# untitled.net
KiCad netlist of a schematic drawn in EAGLE
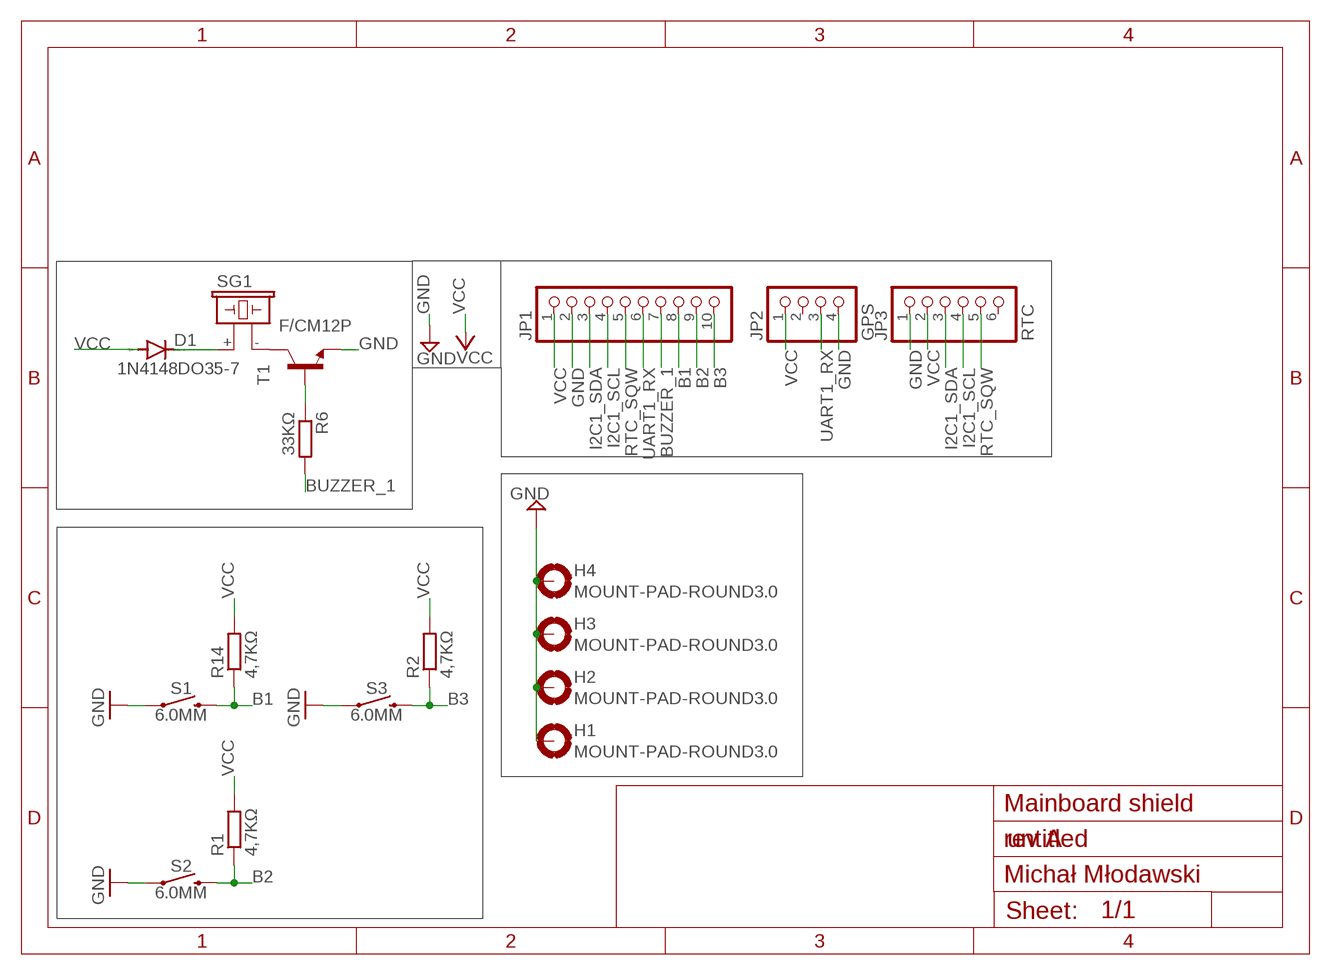
[diagram p0: schematic, sheet 1]

(export (version "E")
  (design (tool "Eeschema 10.0.6"))
  (components
    (comp (ref "D1")
      (value "1N4148DO35-7")
      (footprint "eagle-import:DO35-7")
      (libsource (lib "eagle-import") (part "1N4148DO35-7"))
    )
    (comp (ref "H1")
      (value "MOUNT-PAD-ROUND3.0")
      (footprint "eagle-import:3,0-PAD")
      (libsource (lib "eagle-import") (part "MOUNT-PAD-ROUND3.0"))
    )
    (comp (ref "H2")
      (value "MOUNT-PAD-ROUND3.0")
      (footprint "eagle-import:3,0-PAD")
      (libsource (lib "eagle-import") (part "MOUNT-PAD-ROUND3.0"))
    )
    (comp (ref "H3")
      (value "MOUNT-PAD-ROUND3.0")
      (footprint "eagle-import:3,0-PAD")
      (libsource (lib "eagle-import") (part "MOUNT-PAD-ROUND3.0"))
    )
    (comp (ref "H4")
      (value "MOUNT-PAD-ROUND3.0")
      (footprint "eagle-import:3,0-PAD")
      (libsource (lib "eagle-import") (part "MOUNT-PAD-ROUND3.0"))
    )
    (comp (ref "JP1")
      (value "PINHD-1X10")
      (footprint "eagle-import:1X10")
      (libsource (lib "eagle-import") (part "PINHD-1X10"))
    )
    (comp (ref "JP2")
      (value "GPS")
      (footprint "eagle-import:1X04")
      (libsource (lib "eagle-import") (part "PINHD-1X4"))
    )
    (comp (ref "JP3")
      (value "RTC")
      (footprint "eagle-import:1X06")
      (libsource (lib "eagle-import") (part "PINHD-1X6"))
    )
    (comp (ref "R1")
      (value "4,7KΩ")
      (footprint "eagle-import:R1206")
      (libsource (lib "eagle-import") (part "R-EU_R1206"))
    )
    (comp (ref "R2")
      (value "4,7KΩ")
      (footprint "eagle-import:R1206")
      (libsource (lib "eagle-import") (part "R-EU_R1206"))
    )
    (comp (ref "R6")
      (value "33KΩ")
      (footprint "eagle-import:R1206")
      (libsource (lib "eagle-import") (part "R-EU_R1206"))
    )
    (comp (ref "R14")
      (value "4,7KΩ")
      (footprint "eagle-import:R1206")
      (libsource (lib "eagle-import") (part "R-EU_R1206"))
    )
    (comp (ref "S1")
      (value "6.0MM")
      (footprint "eagle-import:TACTILE_SWITCH_PTH_6.0MM")
      (libsource (lib "eagle-import") (part "MOMENTARY-SWITCH-SPST-PTH-6.0MM"))
    )
    (comp (ref "S2")
      (value "6.0MM")
      (footprint "eagle-import:TACTILE_SWITCH_PTH_6.0MM")
      (libsource (lib "eagle-import") (part "MOMENTARY-SWITCH-SPST-PTH-6.0MM"))
    )
    (comp (ref "S3")
      (value "6.0MM")
      (footprint "eagle-import:TACTILE_SWITCH_PTH_6.0MM")
      (libsource (lib "eagle-import") (part "MOMENTARY-SWITCH-SPST-PTH-6.0MM"))
    )
    (comp (ref "SG1")
      (value "F/CM12P")
      (footprint "eagle-import:F_CM12P")
      (libsource (lib "eagle-import") (part "F/CM12P"))
    )
    (comp (ref "T1")
      (value "BC548-NPN-TO92-CBE")
      (footprint "eagle-import:TO92-CBE")
      (libsource (lib "eagle-import") (part "-NPN-TO92-CBEBC548"))
    )
  )
  (nets
    (net (code "1") (name "/B1") (class "Default")
      (node (ref "JP1") (pin "8") (pinfunction "8_8") (pintype "passive"))
      (node (ref "R14") (pin "1") (pinfunction "1_1") (pintype "passive"))
      (node (ref "S1") (pin "3") (pinfunction "2_3") (pintype "passive"))
    )
    (net (code "2") (name "/B2") (class "Default")
      (node (ref "JP1") (pin "9") (pinfunction "9_9") (pintype "passive"))
      (node (ref "R1") (pin "1") (pinfunction "1_1") (pintype "passive"))
      (node (ref "S2") (pin "3") (pinfunction "2_3") (pintype "passive"))
    )
    (net (code "3") (name "/B3") (class "Default")
      (node (ref "JP1") (pin "10") (pinfunction "10_10") (pintype "passive"))
      (node (ref "R2") (pin "1") (pinfunction "1_1") (pintype "passive"))
      (node (ref "S3") (pin "3") (pinfunction "2_3") (pintype "passive"))
    )
    (net (code "4") (name "/BUZZER_1") (class "Default")
      (node (ref "JP1") (pin "7") (pinfunction "7_7") (pintype "passive"))
      (node (ref "R6") (pin "2") (pinfunction "2_2") (pintype "passive"))
    )
    (net (code "5") (name "/I2C1_SCL") (class "Default")
      (node (ref "JP1") (pin "4") (pinfunction "4_4") (pintype "passive"))
      (node (ref "JP3") (pin "4") (pinfunction "4_4") (pintype "passive"))
    )
    (net (code "6") (name "/I2C1_SDA") (class "Default")
      (node (ref "JP1") (pin "3") (pinfunction "3_3") (pintype "passive"))
      (node (ref "JP3") (pin "3") (pinfunction "3_3") (pintype "passive"))
    )
    (net (code "7") (name "/RTC_SQW") (class "Default")
      (node (ref "JP1") (pin "5") (pinfunction "5_5") (pintype "passive"))
      (node (ref "JP3") (pin "5") (pinfunction "5_5") (pintype "passive"))
    )
    (net (code "8") (name "/UART1_RX") (class "Default")
      (node (ref "JP1") (pin "6") (pinfunction "6_6") (pintype "passive"))
      (node (ref "JP2") (pin "3") (pinfunction "3_3") (pintype "passive"))
    )
    (net (code "9") (name "GND") (class "Default")
      (node (ref "H1") (pin "B3,0") (pinfunction "MOUNT_B3,0") (pintype "passive"))
      (node (ref "H2") (pin "B3,0") (pinfunction "MOUNT_B3,0") (pintype "passive"))
      (node (ref "H3") (pin "B3,0") (pinfunction "MOUNT_B3,0") (pintype "passive"))
      (node (ref "H4") (pin "B3,0") (pinfunction "MOUNT_B3,0") (pintype "passive"))
      (node (ref "JP1") (pin "2") (pinfunction "2_2") (pintype "passive"))
      (node (ref "JP2") (pin "4") (pinfunction "4_4") (pintype "passive"))
      (node (ref "JP3") (pin "1") (pinfunction "1_1") (pintype "passive"))
      (node (ref "S1") (pin "1") (pinfunction "1_1") (pintype "passive"))
      (node (ref "S2") (pin "1") (pinfunction "1_1") (pintype "passive"))
      (node (ref "S3") (pin "1") (pinfunction "1_1") (pintype "passive"))
      (node (ref "T1") (pin "E") (pinfunction "E_E") (pintype "passive"))
    )
    (net (code "10") (name "Net-(R6-Pad1)") (class "Default")
      (node (ref "R6") (pin "1") (pinfunction "1_1") (pintype "passive"))
      (node (ref "T1") (pin "B") (pinfunction "B_B") (pintype "passive"))
    )
    (net (code "11") (name "Net-(SG1-1)") (class "Default")
      (node (ref "D1") (pin "C") (pinfunction "C_C") (pintype "passive"))
      (node (ref "SG1") (pin "+") (pinfunction "1_+") (pintype "passive"))
    )
    (net (code "12") (name "Net-(SG1-2)") (class "Default")
      (node (ref "SG1") (pin "-") (pinfunction "2_-") (pintype "passive"))
      (node (ref "T1") (pin "C") (pinfunction "C_C") (pintype "passive"))
    )
    (net (code "13") (name "VCC") (class "Default")
      (node (ref "D1") (pin "A") (pinfunction "A_A") (pintype "passive"))
      (node (ref "JP1") (pin "1") (pinfunction "1_1") (pintype "passive"))
      (node (ref "JP2") (pin "1") (pinfunction "1_1") (pintype "passive"))
      (node (ref "JP3") (pin "2") (pinfunction "2_2") (pintype "passive"))
      (node (ref "R1") (pin "2") (pinfunction "2_2") (pintype "passive"))
      (node (ref "R14") (pin "2") (pinfunction "2_2") (pintype "passive"))
      (node (ref "R2") (pin "2") (pinfunction "2_2") (pintype "passive"))
    )
    (net (code "14") (name "unconnected-(JP2-Pad2)") (class "Default")
      (node (ref "JP2") (pin "2") (pinfunction "2_2") (pintype "passive"))
    )
    (net (code "15") (name "unconnected-(JP3-Pad6)") (class "Default")
      (node (ref "JP3") (pin "6") (pinfunction "6_6") (pintype "passive"))
    )
  )
)
